# WaterE_mac.net
KiCad netlist of a schematic drawn in EAGLE
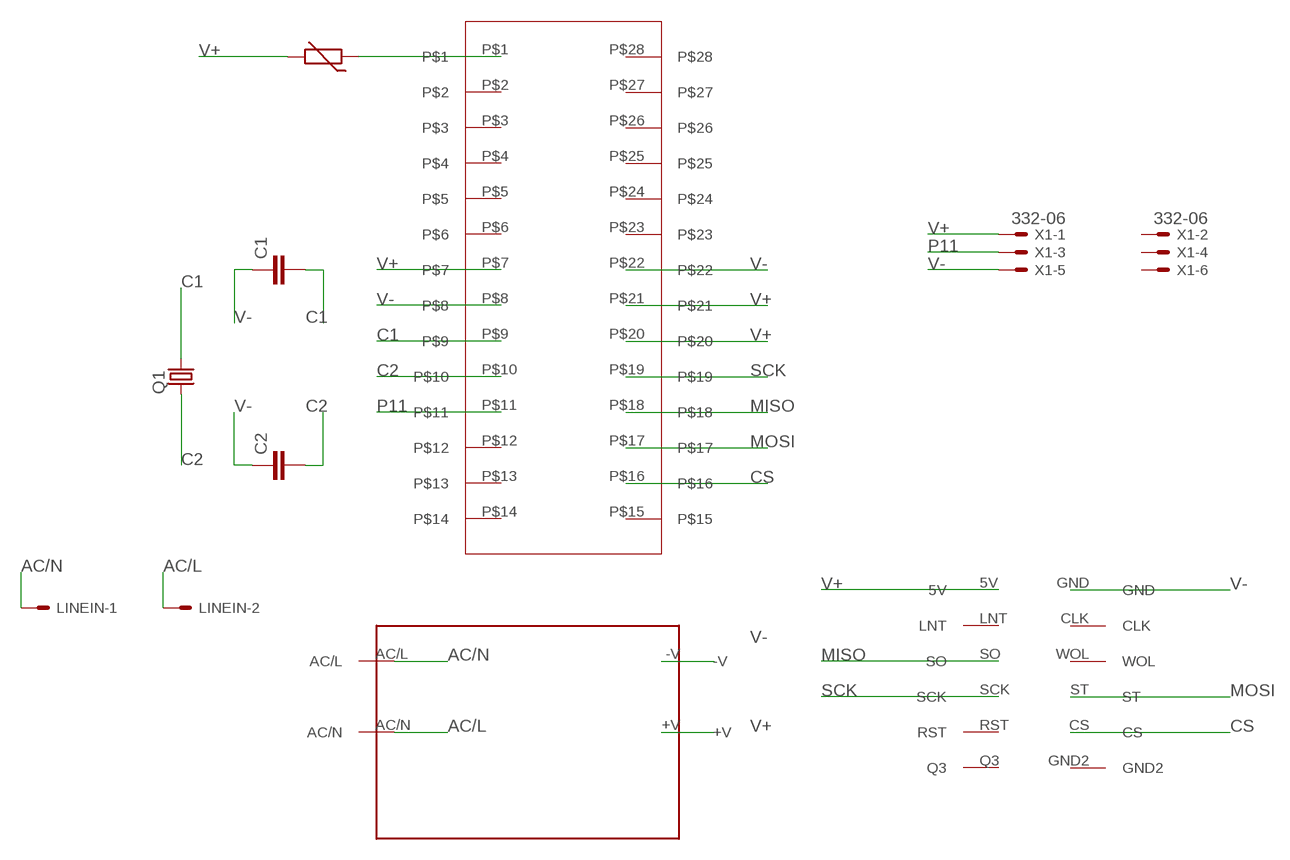
[diagram p0: schematic, sheet 1]

(export (version "E")
  (design (tool "Eeschema 10.0.6"))
  (components
    (comp (ref "C1")
      (value "C-EU025-024X044")
      (footprint "eagle-import:C025-024X044")
      (libsource (lib "eagle-import") (part "C-EU025-024X044"))
    )
    (comp (ref "C2")
      (value "C-EU025-024X044")
      (footprint "eagle-import:C025-024X044")
      (libsource (lib "eagle-import") (part "C-EU025-024X044"))
    )
    (comp (ref "LINEIN")
      (value "AC/L")
      (footprint "eagle-import:332-02")
      (libsource (lib "eagle-import") (part "332-02"))
    )
    (comp (ref "Q1")
      (value "CRYSTALTC26V")
      (footprint "eagle-import:TC26V")
      (libsource (lib "eagle-import") (part "CRYSTALTC26V"))
    )
    (comp (ref "R1")
      (value "THERMISTOR_R-5")
      (footprint "eagle-import:R-5")
      (libsource (lib "eagle-import") (part "THERMISTOR_R-5"))
    )
    (comp (ref "U$1")
      (value "POWER_COMPONENT")
      (footprint "eagle-import:POWER_COMPONENT")
      (libsource (lib "eagle-import") (part "POWER_COMPONENT"))
    )
    (comp (ref "U$2")
      (value "ETHER")
      (footprint "eagle-import:ETHER")
      (libsource (lib "eagle-import") (part "ETHER"))
    )
    (comp (ref "U$4")
      (value "SOCKET_SENIOR")
      (footprint "eagle-import:SOCKET_SENIOR")
      (libsource (lib "eagle-import") (part "SOCKET_SENIOR"))
    )
    (comp (ref "X1")
      (value "332-06")
      (footprint "eagle-import:332-06")
      (libsource (lib "eagle-import") (part "332-06"))
    )
  )
  (nets
    (net (code "1") (name "/AC{slash}L") (class "Default")
      (node (ref "LINEIN") (pin "2") (pinfunction "S_2") (pintype "passive"))
      (node (ref "U$1") (pin "AC/N") (pinfunction "AC/N_AC/N") (pintype "bidirectional"))
    )
    (net (code "2") (name "/AC{slash}N") (class "Default")
      (node (ref "LINEIN") (pin "1") (pinfunction "S_1") (pintype "passive"))
      (node (ref "U$1") (pin "AC/L") (pinfunction "AC/L_AC/L") (pintype "bidirectional"))
    )
    (net (code "3") (name "/C1") (class "Default")
      (node (ref "C1") (pin "2") (pinfunction "2_2") (pintype "passive"))
      (node (ref "Q1") (pin "2") (pinfunction "2_2") (pintype "passive"))
      (node (ref "U$4") (pin "P$9") (pinfunction "P$9_P$9") (pintype "bidirectional"))
    )
    (net (code "4") (name "/C2") (class "Default")
      (node (ref "C2") (pin "2") (pinfunction "2_2") (pintype "passive"))
      (node (ref "Q1") (pin "1") (pinfunction "1_1") (pintype "passive"))
      (node (ref "U$4") (pin "P$10") (pinfunction "P$10_P$10") (pintype "bidirectional"))
    )
    (net (code "5") (name "/CS") (class "Default")
      (node (ref "U$2") (pin "CS") (pinfunction "CS_CS") (pintype "bidirectional"))
      (node (ref "U$4") (pin "P$16") (pinfunction "P$16_P$16") (pintype "bidirectional"))
    )
    (net (code "6") (name "/MISO") (class "Default")
      (node (ref "U$2") (pin "SO") (pinfunction "SO_SO") (pintype "bidirectional"))
      (node (ref "U$4") (pin "P$18") (pinfunction "P$18_P$18") (pintype "bidirectional"))
    )
    (net (code "7") (name "/MOSI") (class "Default")
      (node (ref "U$2") (pin "ST") (pinfunction "ST_ST") (pintype "bidirectional"))
      (node (ref "U$4") (pin "P$17") (pinfunction "P$17_P$17") (pintype "bidirectional"))
    )
    (net (code "8") (name "/P11") (class "Default")
      (node (ref "U$4") (pin "P$11") (pinfunction "P$11_P$11") (pintype "bidirectional"))
      (node (ref "X1") (pin "3") (pinfunction "S_3") (pintype "passive"))
    )
    (net (code "9") (name "/SCK") (class "Default")
      (node (ref "U$2") (pin "SCK") (pinfunction "SCK_SCK") (pintype "bidirectional"))
      (node (ref "U$4") (pin "P$19") (pinfunction "P$19_P$19") (pintype "bidirectional"))
    )
    (net (code "10") (name "/V+") (class "Default")
      (node (ref "R1") (pin "2") (pinfunction "2_2") (pintype "passive"))
      (node (ref "U$1") (pin "+V") (pinfunction "+V_+V") (pintype "bidirectional"))
      (node (ref "U$2") (pin "5V") (pinfunction "5V_5V") (pintype "bidirectional"))
      (node (ref "U$4") (pin "P$20") (pinfunction "P$20_P$20") (pintype "bidirectional"))
      (node (ref "U$4") (pin "P$21") (pinfunction "P$21_P$21") (pintype "bidirectional"))
      (node (ref "U$4") (pin "P$7") (pinfunction "P$7_P$7") (pintype "bidirectional"))
      (node (ref "X1") (pin "1") (pinfunction "S_1") (pintype "passive"))
    )
    (net (code "11") (name "/V-") (class "Default")
      (node (ref "C1") (pin "1") (pinfunction "1_1") (pintype "passive"))
      (node (ref "C2") (pin "1") (pinfunction "1_1") (pintype "passive"))
      (node (ref "U$1") (pin "-V") (pinfunction "-V_-V") (pintype "bidirectional"))
      (node (ref "U$2") (pin "GND") (pinfunction "GND_GND") (pintype "bidirectional"))
      (node (ref "U$4") (pin "P$22") (pinfunction "P$22_P$22") (pintype "bidirectional"))
      (node (ref "U$4") (pin "P$8") (pinfunction "P$8_P$8") (pintype "bidirectional"))
      (node (ref "X1") (pin "5") (pinfunction "S_5") (pintype "passive"))
    )
    (net (code "12") (name "Net-(R1-Pad1)") (class "Default")
      (node (ref "R1") (pin "1") (pinfunction "1_1") (pintype "passive"))
      (node (ref "U$4") (pin "P$1") (pinfunction "P$1_P$1") (pintype "bidirectional"))
    )
    (net (code "13") (name "unconnected-(U$2-PadCLK)") (class "Default")
      (node (ref "U$2") (pin "CLK") (pinfunction "CLK_CLK") (pintype "bidirectional"))
    )
    (net (code "14") (name "unconnected-(U$2-PadGND2)") (class "Default")
      (node (ref "U$2") (pin "GND2") (pinfunction "GND2_GND2") (pintype "bidirectional"))
    )
    (net (code "15") (name "unconnected-(U$2-PadLNT)") (class "Default")
      (node (ref "U$2") (pin "LNT") (pinfunction "LNT_LNT") (pintype "bidirectional"))
    )
    (net (code "16") (name "unconnected-(U$2-PadQ3)") (class "Default")
      (node (ref "U$2") (pin "Q3") (pinfunction "Q3_Q3") (pintype "bidirectional"))
    )
    (net (code "17") (name "unconnected-(U$2-PadRST)") (class "Default")
      (node (ref "U$2") (pin "RST") (pinfunction "RST_RST") (pintype "bidirectional"))
    )
    (net (code "18") (name "unconnected-(U$2-PadWOL)") (class "Default")
      (node (ref "U$2") (pin "WOL") (pinfunction "WOL_WOL") (pintype "bidirectional"))
    )
    (net (code "19") (name "unconnected-(U$4-PadP$2)") (class "Default")
      (node (ref "U$4") (pin "P$2") (pinfunction "P$2_P$2") (pintype "bidirectional"))
    )
    (net (code "20") (name "unconnected-(U$4-PadP$3)") (class "Default")
      (node (ref "U$4") (pin "P$3") (pinfunction "P$3_P$3") (pintype "bidirectional"))
    )
    (net (code "21") (name "unconnected-(U$4-PadP$4)") (class "Default")
      (node (ref "U$4") (pin "P$4") (pinfunction "P$4_P$4") (pintype "bidirectional"))
    )
    (net (code "22") (name "unconnected-(U$4-PadP$5)") (class "Default")
      (node (ref "U$4") (pin "P$5") (pinfunction "P$5_P$5") (pintype "bidirectional"))
    )
    (net (code "23") (name "unconnected-(U$4-PadP$6)") (class "Default")
      (node (ref "U$4") (pin "P$6") (pinfunction "P$6_P$6") (pintype "bidirectional"))
    )
    (net (code "24") (name "unconnected-(U$4-PadP$12)") (class "Default")
      (node (ref "U$4") (pin "P$12") (pinfunction "P$12_P$12") (pintype "bidirectional"))
    )
    (net (code "25") (name "unconnected-(U$4-PadP$13)") (class "Default")
      (node (ref "U$4") (pin "P$13") (pinfunction "P$13_P$13") (pintype "bidirectional"))
    )
    (net (code "26") (name "unconnected-(U$4-PadP$14)") (class "Default")
      (node (ref "U$4") (pin "P$14") (pinfunction "P$14_P$14") (pintype "bidirectional"))
    )
    (net (code "27") (name "unconnected-(U$4-PadP$15)") (class "Default")
      (node (ref "U$4") (pin "P$15") (pinfunction "P$15_P$15") (pintype "bidirectional"))
    )
    (net (code "28") (name "unconnected-(U$4-PadP$23)") (class "Default")
      (node (ref "U$4") (pin "P$23") (pinfunction "P$23_P$23") (pintype "bidirectional"))
    )
    (net (code "29") (name "unconnected-(U$4-PadP$24)") (class "Default")
      (node (ref "U$4") (pin "P$24") (pinfunction "P$24_P$24") (pintype "bidirectional"))
    )
    (net (code "30") (name "unconnected-(U$4-PadP$25)") (class "Default")
      (node (ref "U$4") (pin "P$25") (pinfunction "P$25_P$25") (pintype "bidirectional"))
    )
    (net (code "31") (name "unconnected-(U$4-PadP$26)") (class "Default")
      (node (ref "U$4") (pin "P$26") (pinfunction "P$26_P$26") (pintype "bidirectional"))
    )
    (net (code "32") (name "unconnected-(U$4-PadP$27)") (class "Default")
      (node (ref "U$4") (pin "P$27") (pinfunction "P$27_P$27") (pintype "bidirectional"))
    )
    (net (code "33") (name "unconnected-(U$4-PadP$28)") (class "Default")
      (node (ref "U$4") (pin "P$28") (pinfunction "P$28_P$28") (pintype "bidirectional"))
    )
    (net (code "34") (name "unconnected-(X1B-S-Pad2)") (class "Default")
      (node (ref "X1") (pin "2") (pinfunction "S_2") (pintype "passive"))
    )
    (net (code "35") (name "unconnected-(X1D-S-Pad4)") (class "Default")
      (node (ref "X1") (pin "4") (pinfunction "S_4") (pintype "passive"))
    )
    (net (code "36") (name "unconnected-(X1F-S-Pad6)") (class "Default")
      (node (ref "X1") (pin "6") (pinfunction "S_6") (pintype "passive"))
    )
  )
)
